# MCU.net
KiCad netlist of a schematic drawn in Altium Designer
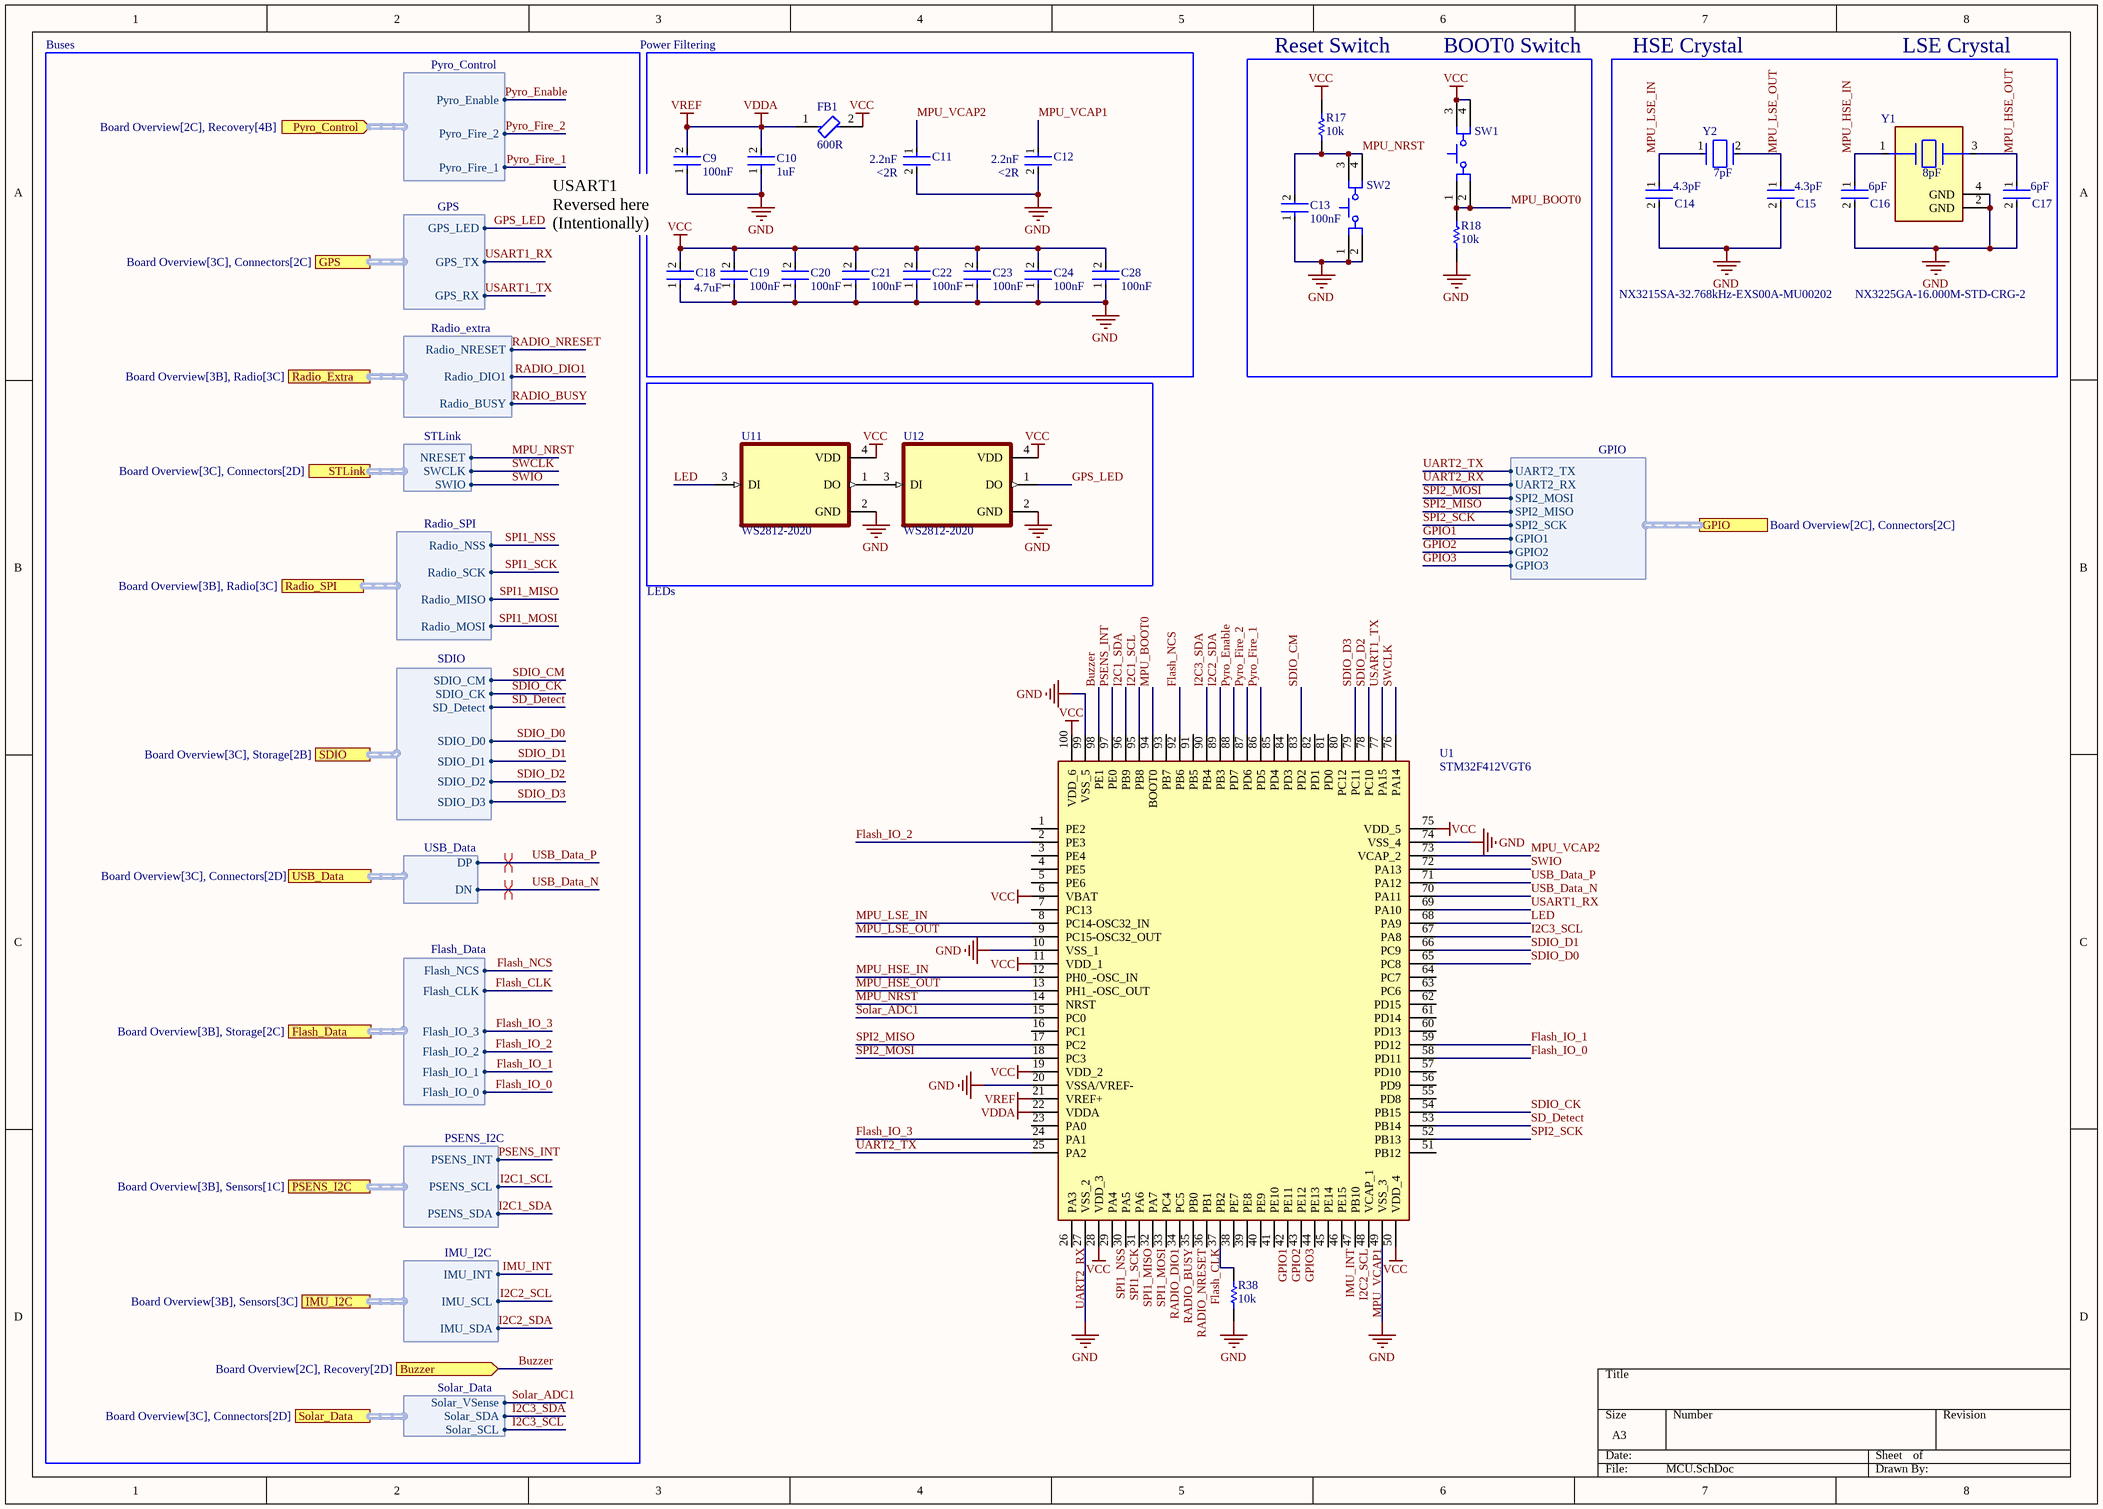
[diagram p0: MCU.SchDoc]

(export (version "E")
  (design (tool "Eeschema 10.0.6"))
  (components
    (comp (ref "C9")
      (value "100nF")
      (footprint "FP-0603-L_1_6_0_15-W_0_81-IPC_C")
      (description "Generic 0603 Capacitor")
      (fields (field (name "LCSC PART #") "C14663") (field (name "TOLERANCE") "10%"))
      (libsource (lib "StrathSEDS") (part "02cd4be3c70576c341d710602a673aa"))
    )
    (comp (ref "C10")
      (value "1uF")
      (footprint "FP-0603-L_1_6_0_15-W_0_81-IPC_C")
      (description "Generic 0603 Capacitor")
      (fields (field (name "LCSC PART #") "C15849") (field (name "TOLERANCE") "10%"))
      (libsource (lib "StrathSEDS") (part "02cd4be3c70576c341d710602a673aa"))
    )
    (comp (ref "C11")
      (value "2.2nF")
      (footprint "FP-0603-L_1_6_0_15-W_0_81-IPC_C")
      (description "Generic 0603 Capacitor")
      (fields
        (field (name "LCSC PART #") "C1604")
        (field (name "TOLERANCE") "10%")
        (field (name "ESR") "<2R")
      )
      (libsource (lib "StrathSEDS") (part "02cd4be3c70576c341d710602a673aa"))
    )
    (comp (ref "C12")
      (value "2.2nF")
      (footprint "FP-0603-L_1_6_0_15-W_0_81-IPC_C")
      (description "Generic 0603 Capacitor")
      (fields
        (field (name "LCSC PART #") "C1604")
        (field (name "TOLERANCE") "10%")
        (field (name "ESR") "<2R")
      )
      (libsource (lib "StrathSEDS") (part "02cd4be3c70576c341d710602a673aa"))
    )
    (comp (ref "C13")
      (value "100nF")
      (footprint "FP-0603-L_1_6_0_15-W_0_81-IPC_C")
      (description "Generic 0603 Capacitor")
      (fields (field (name "LCSC PART #") "C14663") (field (name "TOLERANCE") "10%"))
      (libsource (lib "StrathSEDS") (part "02cd4be3c70576c341d710602a673aa"))
    )
    (comp (ref "C14")
      (value "4.3pF")
      (footprint "FP-CL10-IPC_B")
      (description "50V 4.3pF C0G ±0.25pF 0603 Multilayer Ceramic Capacitors MLCC - SMD/SMT ROHS")
      (fields (field (name "LCSC PART #") "C59526") (field (name "Comment") "0603CG4R3C500NT"))
      (libsource (lib "StrathSEDS Mach 22") (part "b4654b650e69147ec39a6b967a45e02"))
    )
    (comp (ref "C15")
      (value "4.3pF")
      (footprint "FP-CL10-IPC_B")
      (description "50V 4.3pF C0G ±0.25pF 0603 Multilayer Ceramic Capacitors MLCC - SMD/SMT ROHS")
      (fields (field (name "LCSC PART #") "C59526") (field (name "Comment") "0603CG4R3C500NT"))
      (libsource (lib "StrathSEDS Mach 22") (part "b4654b650e69147ec39a6b967a45e02"))
    )
    (comp (ref "C16")
      (value "6pF")
      (footprint "FP-CL10-IPC_B")
      (description "CAP CER 6PF 50V C0G/NP0 0603")
      (fields (field (name "LCSC PART #") "C37474") (field (name "Comment") "CL10C060DB8NNNC"))
      (libsource (lib "StrathSEDS Mach 22") (part "b4654b650e69147ec39a6b967a45e02"))
    )
    (comp (ref "C17")
      (value "6pF")
      (footprint "FP-CL10-IPC_B")
      (description "CAP CER 6PF 50V C0G/NP0 0603")
      (fields (field (name "LCSC PART #") "C37474") (field (name "Comment") "CL10C060DB8NNNC"))
      (libsource (lib "StrathSEDS Mach 22") (part "b4654b650e69147ec39a6b967a45e02"))
    )
    (comp (ref "C18")
      (value "4.7uF")
      (footprint "FP-0603-L_1_6_0_15-W_0_81-IPC_C")
      (description "Generic 0603 Capacitor")
      (fields (field (name "LCSC PART #") "C53987") (field (name "TOLERANCE") "10%"))
      (libsource (lib "StrathSEDS") (part "02cd4be3c70576c341d710602a673aa"))
    )
    (comp (ref "C19")
      (value "100nF")
      (footprint "FP-0603-L_1_6_0_15-W_0_81-IPC_C")
      (description "Generic 0603 Capacitor")
      (fields (field (name "LCSC PART #") "C14663") (field (name "TOLERANCE") "10%"))
      (libsource (lib "StrathSEDS") (part "02cd4be3c70576c341d710602a673aa"))
    )
    (comp (ref "C20")
      (value "100nF")
      (footprint "FP-0603-L_1_6_0_15-W_0_81-IPC_C")
      (description "Generic 0603 Capacitor")
      (fields (field (name "LCSC PART #") "C14663") (field (name "TOLERANCE") "10%"))
      (libsource (lib "StrathSEDS") (part "02cd4be3c70576c341d710602a673aa"))
    )
    (comp (ref "C21")
      (value "100nF")
      (footprint "FP-0603-L_1_6_0_15-W_0_81-IPC_C")
      (description "Generic 0603 Capacitor")
      (fields (field (name "LCSC PART #") "C14663") (field (name "TOLERANCE") "10%"))
      (libsource (lib "StrathSEDS") (part "02cd4be3c70576c341d710602a673aa"))
    )
    (comp (ref "C22")
      (value "100nF")
      (footprint "FP-0603-L_1_6_0_15-W_0_81-IPC_C")
      (description "Generic 0603 Capacitor")
      (fields (field (name "LCSC PART #") "C14663") (field (name "TOLERANCE") "10%"))
      (libsource (lib "StrathSEDS") (part "02cd4be3c70576c341d710602a673aa"))
    )
    (comp (ref "C23")
      (value "100nF")
      (footprint "FP-0603-L_1_6_0_15-W_0_81-IPC_C")
      (description "Generic 0603 Capacitor")
      (fields (field (name "LCSC PART #") "C14663") (field (name "TOLERANCE") "10%"))
      (libsource (lib "StrathSEDS") (part "02cd4be3c70576c341d710602a673aa"))
    )
    (comp (ref "C24")
      (value "100nF")
      (footprint "FP-0603-L_1_6_0_15-W_0_81-IPC_C")
      (description "Generic 0603 Capacitor")
      (fields (field (name "LCSC PART #") "C14663") (field (name "TOLERANCE") "10%"))
      (libsource (lib "StrathSEDS") (part "02cd4be3c70576c341d710602a673aa"))
    )
    (comp (ref "C28")
      (value "100nF")
      (footprint "FP-0603-L_1_6_0_15-W_0_81-IPC_C")
      (description "Generic 0603 Capacitor")
      (fields (field (name "LCSC PART #") "C14663") (field (name "TOLERANCE") "10%"))
      (libsource (lib "StrathSEDS") (part "02cd4be3c70576c341d710602a673aa"))
    )
    (comp (ref "FB1")
      (value "600R")
      (footprint "FP-BLM18-0_15-0_1-t0_6-IPC_B")
      (description "0603 600Ω ±25% DCR=0.45Ω 0.2A")
      (fields (field (name "LCSC PART #") "C1002") (field (name "Comment") "GZ1608D601TF"))
      (libsource (lib "StrathSEDS Mach 22") (part "5f30dd21d616792df468990f7003faa"))
    )
    (comp (ref "R17")
      (value "10k")
      (footprint "RESC1608X55X25ML10T15")
      (fields (field (name "LCSC PART #") "C25804") (field (name "Comment") "0603WAF1002T5E"))
      (libsource (lib "StrathSEDS Mach 22") (part "RES-2"))
    )
    (comp (ref "R18")
      (value "10k")
      (footprint "RESC1608X55X25ML10T15")
      (fields (field (name "LCSC PART #") "C25804") (field (name "Comment") "0603WAF1002T5E"))
      (libsource (lib "StrathSEDS Mach 22") (part "RES-2"))
    )
    (comp (ref "R38")
      (value "10k")
      (footprint "RESC1609X50X30ML8T20")
      (description "Generic 0603 Resistor")
      (fields (field (name "TOLERANCE") "0%") (field (name "LCSC PART #") "C25804"))
      (libsource (lib "StrathSEDS") (part "RES-2"))
    )
    (comp (ref "SW1")
      (value "PTS645SM43SMTR92LFS")
      (footprint "CKCP-PTS645S_V")
      (description "Switch Tactile N.O. SPST Round Button Gull Wing 0.05A 12VDC 100000Cycles 1.57N SMD T/R")
      (fields (field (name "LCSC PART #") "C221880"))
      (libsource (lib "StrathSEDS Mach 22") (part "SW-SPST-NO-4"))
    )
    (comp (ref "SW2")
      (value "PTS645SM43SMTR92LFS")
      (footprint "CKCP-PTS645S_V")
      (description "Switch Tactile N.O. SPST Round Button Gull Wing 0.05A 12VDC 100000Cycles 1.57N SMD T/R")
      (fields (field (name "LCSC PART #") "C221880"))
      (libsource (lib "StrathSEDS Mach 22") (part "SW-SPST-NO-4"))
    )
    (comp (ref "U1")
      (value "STM32F412VGT6")
      (footprint "QFP50P1600X1600X160-100N")
      (fields (field (name "MOUSER PART NUMBER") "511-STM32F412VGT6") (field (name "LCSC PART #") "C727951"))
      (libsource (lib "StrathSEDS") (part "STM32F412VGT6"))
    )
    (comp (ref "U11")
      (value "WS2812-2020")
      (footprint "LED_WS2812-2020")
      (description "Intelligent control LED light source, SMD-4")
      (fields (field (name "MF") "Worldsemi") (field (name "LCSC PART #") "C965555"))
      (libsource (lib "StrathSEDS") (part "WS2812-2020"))
    )
    (comp (ref "U12")
      (value "WS2812-2020")
      (footprint "LED_WS2812-2020")
      (description "Intelligent control LED light source, SMD-4")
      (fields (field (name "MF") "Worldsemi") (field (name "LCSC PART #") "C965555"))
      (libsource (lib "StrathSEDS") (part "WS2812-2020"))
    )
    (comp (ref "Y1")
      (value "NX3225GA-16.000M-STD-CRG-2")
      (footprint "FP-NX3225GA-MFG")
      (description "Crystal 16MHz ±20ppm (Tol) ±30ppm (Stability) 8pF FUND 80Ohm Automotive 4-Pin SMD")
      (fields (field (name "LCSC PART #") "C156247") (field (name "ALTIUM_VALUE") "8pF"))
      (libsource (lib "StrathSEDS Mach 22") (part "6320effb7d3e443b36bf79d8ebe02e5"))
    )
    (comp (ref "Y2")
      (value "NX3215SA-32.768kHz-EXS00A-MU00202")
      (footprint "FP-NX3215SA-MFG")
      (description "Crystal 32.7680KHZ 7PF SMD")
      (fields (field (name "LCSC PART #") "C280830") (field (name "ALTIUM_VALUE") "7pF"))
      (libsource (lib "StrathSEDS Mach 22") (part "c23a69dc6c9e2f18f2079038eb95dd1"))
    )
  )
  (nets
    (net (code "13") (name "/Buzzer") (class "Default")
      (node (ref "U1") (pin "98") (pinfunction "PE1_98") (pintype "passive"))
    )
    (net (code "14") (name "/Flash_CLK") (class "Default")
      (node (ref "U1") (pin "36") (pinfunction "PB1_36") (pintype "passive"))
    )
    (net (code "15") (name "/Flash_IO_0") (class "Default")
      (node (ref "U1") (pin "58") (pinfunction "PD11_58") (pintype "passive"))
    )
    (net (code "16") (name "/Flash_IO_1") (class "Default")
      (node (ref "U1") (pin "59") (pinfunction "PD12_59") (pintype "passive"))
    )
    (net (code "17") (name "/Flash_IO_2") (class "Default")
      (node (ref "U1") (pin "2") (pinfunction "PE3_2") (pintype "passive"))
    )
    (net (code "18") (name "/Flash_IO_3") (class "Default")
      (node (ref "U1") (pin "24") (pinfunction "PA1_24") (pintype "passive"))
    )
    (net (code "19") (name "/Flash_NCS") (class "Default")
      (node (ref "U1") (pin "92") (pinfunction "PB6_92") (pintype "passive"))
    )
    (net (code "20") (name "/GPIO1") (class "Default")
      (node (ref "U1") (pin "41") (pinfunction "PE10_41") (pintype "passive"))
    )
    (net (code "21") (name "/GPIO2") (class "Default")
      (node (ref "U1") (pin "42") (pinfunction "PE11_42") (pintype "passive"))
    )
    (net (code "22") (name "/GPIO3") (class "Default")
      (node (ref "U1") (pin "43") (pinfunction "PE12_43") (pintype "passive"))
    )
    (net (code "23") (name "/GPS_LED") (class "Default")
      (node (ref "U12") (pin "1") (pinfunction "DO_1") (pintype "output"))
    )
    (net (code "24") (name "/I2C1_SCL") (class "Default")
      (node (ref "U1") (pin "95") (pinfunction "PB8_95") (pintype "passive"))
    )
    (net (code "25") (name "/I2C1_SDA") (class "Default")
      (node (ref "U1") (pin "96") (pinfunction "PB9_96") (pintype "passive"))
    )
    (net (code "26") (name "/I2C2_SCL") (class "Default")
      (node (ref "U1") (pin "47") (pinfunction "PB10_47") (pintype "passive"))
    )
    (net (code "27") (name "/I2C2_SDA") (class "Default")
      (node (ref "U1") (pin "89") (pinfunction "PB3_89") (pintype "passive"))
    )
    (net (code "28") (name "/I2C3_SCL") (class "Default")
      (node (ref "U1") (pin "67") (pinfunction "PA8_67") (pintype "passive"))
    )
    (net (code "29") (name "/I2C3_SDA") (class "Default")
      (node (ref "U1") (pin "90") (pinfunction "PB4_90") (pintype "passive"))
    )
    (net (code "30") (name "/IMU_INT") (class "Default")
      (node (ref "U1") (pin "46") (pinfunction "PE15_46") (pintype "passive"))
    )
    (net (code "31") (name "/LED") (class "Default")
      (node (ref "U1") (pin "68") (pinfunction "PA9_68") (pintype "passive"))
      (node (ref "U11") (pin "3") (pinfunction "DI_3") (pintype "input"))
    )
    (net (code "32") (name "/MPU_BOOT0") (class "Default")
      (node (ref "R18") (pin "2") (pinfunction "2_2") (pintype "passive"))
      (node (ref "SW1") (pin "1") (pinfunction "1_1") (pintype "passive"))
      (node (ref "SW1") (pin "2") (pinfunction "2_2") (pintype "passive"))
      (node (ref "U1") (pin "94") (pinfunction "BOOT0_94") (pintype "passive"))
    )
    (net (code "33") (name "/MPU_HSE_IN") (class "Default")
      (node (ref "C16") (pin "1") (pinfunction "1_1") (pintype "passive"))
      (node (ref "U1") (pin "12") (pinfunction "PH0_-OSC_IN_12") (pintype "passive"))
      (node (ref "Y1") (pin "1") (pinfunction "1_1") (pintype "passive"))
    )
    (net (code "34") (name "/MPU_HSE_OUT") (class "Default")
      (node (ref "C17") (pin "1") (pinfunction "1_1") (pintype "passive"))
      (node (ref "U1") (pin "13") (pinfunction "PH1_-OSC_OUT_13") (pintype "passive"))
      (node (ref "Y1") (pin "3") (pinfunction "3_3") (pintype "passive"))
    )
    (net (code "35") (name "/MPU_LSE_IN") (class "Default")
      (node (ref "C14") (pin "1") (pinfunction "1_1") (pintype "passive"))
      (node (ref "U1") (pin "8") (pinfunction "PC14-OSC32_IN_8") (pintype "passive"))
      (node (ref "Y2") (pin "1") (pinfunction "1_1") (pintype "passive"))
    )
    (net (code "36") (name "/MPU_LSE_OUT") (class "Default")
      (node (ref "C15") (pin "1") (pinfunction "1_1") (pintype "passive"))
      (node (ref "U1") (pin "9") (pinfunction "PC15-OSC32_OUT_9") (pintype "passive"))
      (node (ref "Y2") (pin "2") (pinfunction "2_2") (pintype "passive"))
    )
    (net (code "37") (name "/MPU_NRST") (class "Default")
      (node (ref "C13") (pin "2") (pinfunction "2_2") (pintype "passive"))
      (node (ref "R17") (pin "1") (pinfunction "1_1") (pintype "passive"))
      (node (ref "SW2") (pin "3") (pinfunction "3_3") (pintype "passive"))
      (node (ref "SW2") (pin "4") (pinfunction "4_4") (pintype "passive"))
      (node (ref "U1") (pin "14") (pinfunction "NRST_14") (pintype "passive"))
    )
    (net (code "38") (name "/MPU_VCAP1") (class "Default")
      (node (ref "C12") (pin "1") (pinfunction "1_1") (pintype "passive"))
      (node (ref "U1") (pin "48") (pinfunction "VCAP_1_48") (pintype "passive"))
    )
    (net (code "39") (name "/MPU_VCAP2") (class "Default")
      (node (ref "C11") (pin "1") (pinfunction "1_1") (pintype "passive"))
      (node (ref "U1") (pin "73") (pinfunction "VCAP_2_73") (pintype "passive"))
    )
    (net (code "40") (name "/PSENS_INT") (class "Default")
      (node (ref "U1") (pin "97") (pinfunction "PE0_97") (pintype "passive"))
    )
    (net (code "41") (name "/Pyro_Enable") (class "Default")
      (node (ref "U1") (pin "88") (pinfunction "PD7_88") (pintype "passive"))
    )
    (net (code "42") (name "/Pyro_Fire_1") (class "Default")
      (node (ref "U1") (pin "86") (pinfunction "PD5_86") (pintype "passive"))
    )
    (net (code "43") (name "/Pyro_Fire_2") (class "Default")
      (node (ref "U1") (pin "87") (pinfunction "PD6_87") (pintype "passive"))
    )
    (net (code "44") (name "/RADIO_BUSY") (class "Default")
      (node (ref "U1") (pin "34") (pinfunction "PC5_34") (pintype "passive"))
    )
    (net (code "45") (name "/RADIO_DIO1") (class "Default")
      (node (ref "U1") (pin "33") (pinfunction "PC4_33") (pintype "passive"))
    )
    (net (code "46") (name "/RADIO_NRESET") (class "Default")
      (node (ref "U1") (pin "35") (pinfunction "PB0_35") (pintype "passive"))
    )
    (net (code "47") (name "/SDIO_CK") (class "Default")
      (node (ref "U1") (pin "54") (pinfunction "PB15_54") (pintype "passive"))
    )
    (net (code "48") (name "/SDIO_CM") (class "Default")
      (node (ref "U1") (pin "83") (pinfunction "PD2_83") (pintype "passive"))
    )
    (net (code "49") (name "/SDIO_D0") (class "Default")
      (node (ref "U1") (pin "65") (pinfunction "PC8_65") (pintype "passive"))
    )
    (net (code "50") (name "/SDIO_D1") (class "Default")
      (node (ref "U1") (pin "66") (pinfunction "PC9_66") (pintype "passive"))
    )
    (net (code "51") (name "/SDIO_D2") (class "Default")
      (node (ref "U1") (pin "78") (pinfunction "PC10_78") (pintype "passive"))
    )
    (net (code "52") (name "/SDIO_D3") (class "Default")
      (node (ref "U1") (pin "79") (pinfunction "PC11_79") (pintype "passive"))
    )
    (net (code "53") (name "/SD_Detect") (class "Default")
      (node (ref "U1") (pin "53") (pinfunction "PB14_53") (pintype "passive"))
    )
    (net (code "54") (name "/SPI1_MISO") (class "Default")
      (node (ref "U1") (pin "31") (pinfunction "PA6_31") (pintype "passive"))
    )
    (net (code "55") (name "/SPI1_MOSI") (class "Default")
      (node (ref "U1") (pin "32") (pinfunction "PA7_32") (pintype "passive"))
    )
    (net (code "56") (name "/SPI1_NSS") (class "Default")
      (node (ref "U1") (pin "29") (pinfunction "PA4_29") (pintype "passive"))
    )
    (net (code "57") (name "/SPI1_SCK") (class "Default")
      (node (ref "U1") (pin "30") (pinfunction "PA5_30") (pintype "passive"))
    )
    (net (code "58") (name "/SPI2_MISO") (class "Default")
      (node (ref "U1") (pin "17") (pinfunction "PC2_17") (pintype "passive"))
    )
    (net (code "59") (name "/SPI2_MOSI") (class "Default")
      (node (ref "U1") (pin "18") (pinfunction "PC3_18") (pintype "passive"))
    )
    (net (code "60") (name "/SPI2_SCK") (class "Default")
      (node (ref "U1") (pin "52") (pinfunction "PB13_52") (pintype "passive"))
    )
    (net (code "61") (name "/SWCLK") (class "Default")
      (node (ref "U1") (pin "76") (pinfunction "PA14_76") (pintype "passive"))
    )
    (net (code "62") (name "/SWIO") (class "Default")
      (node (ref "U1") (pin "72") (pinfunction "PA13_72") (pintype "passive"))
    )
    (net (code "63") (name "/Solar_ADC1") (class "Default")
      (node (ref "U1") (pin "15") (pinfunction "PC0_15") (pintype "passive"))
    )
    (net (code "64") (name "/UART2_RX") (class "Default")
      (node (ref "U1") (pin "26") (pinfunction "PA3_26") (pintype "passive"))
    )
    (net (code "65") (name "/UART2_TX") (class "Default")
      (node (ref "U1") (pin "25") (pinfunction "PA2_25") (pintype "passive"))
    )
    (net (code "66") (name "/USART1_RX") (class "Default")
      (node (ref "U1") (pin "69") (pinfunction "PA10_69") (pintype "passive"))
    )
    (net (code "67") (name "/USART1_TX") (class "Default")
      (node (ref "U1") (pin "77") (pinfunction "PA15_77") (pintype "passive"))
    )
    (net (code "68") (name "/USB_Data_N") (class "Default")
      (node (ref "U1") (pin "70") (pinfunction "PA11_70") (pintype "passive"))
    )
    (net (code "69") (name "/USB_Data_P") (class "Default")
      (node (ref "U1") (pin "71") (pinfunction "PA12_71") (pintype "passive"))
    )
    (net (code "82") (name "GND") (class "Default")
      (node (ref "C10") (pin "1") (pinfunction "1_1") (pintype "passive"))
      (node (ref "C11") (pin "2") (pinfunction "2_2") (pintype "passive"))
      (node (ref "C12") (pin "2") (pinfunction "2_2") (pintype "passive"))
      (node (ref "C13") (pin "1") (pinfunction "1_1") (pintype "passive"))
      (node (ref "C14") (pin "2") (pinfunction "2_2") (pintype "passive"))
      (node (ref "C15") (pin "2") (pinfunction "2_2") (pintype "passive"))
      (node (ref "C16") (pin "2") (pinfunction "2_2") (pintype "passive"))
      (node (ref "C17") (pin "2") (pinfunction "2_2") (pintype "passive"))
      (node (ref "C18") (pin "1") (pinfunction "1_1") (pintype "passive"))
      (node (ref "C19") (pin "1") (pinfunction "1_1") (pintype "passive"))
      (node (ref "C20") (pin "1") (pinfunction "1_1") (pintype "passive"))
      (node (ref "C21") (pin "1") (pinfunction "1_1") (pintype "passive"))
      (node (ref "C22") (pin "1") (pinfunction "1_1") (pintype "passive"))
      (node (ref "C23") (pin "1") (pinfunction "1_1") (pintype "passive"))
      (node (ref "C24") (pin "1") (pinfunction "1_1") (pintype "passive"))
      (node (ref "C28") (pin "1") (pinfunction "1_1") (pintype "passive"))
      (node (ref "C9") (pin "1") (pinfunction "1_1") (pintype "passive"))
      (node (ref "R18") (pin "1") (pinfunction "1_1") (pintype "passive"))
      (node (ref "R38") (pin "1") (pinfunction "1_1") (pintype "passive"))
      (node (ref "SW2") (pin "1") (pinfunction "1_1") (pintype "passive"))
      (node (ref "SW2") (pin "2") (pinfunction "2_2") (pintype "passive"))
      (node (ref "U1") (pin "10") (pinfunction "VSS_1_10") (pintype "passive"))
      (node (ref "U1") (pin "20") (pinfunction "VSSA/VREF-_20") (pintype "passive"))
      (node (ref "U1") (pin "27") (pinfunction "VSS_2_27") (pintype "passive"))
      (node (ref "U1") (pin "49") (pinfunction "VSS_3_49") (pintype "passive"))
      (node (ref "U1") (pin "74") (pinfunction "VSS_4_74") (pintype "passive"))
      (node (ref "U1") (pin "99") (pinfunction "VSS_5_99") (pintype "passive"))
      (node (ref "U11") (pin "2") (pinfunction "GND_2") (pintype "power_in"))
      (node (ref "U12") (pin "2") (pinfunction "GND_2") (pintype "power_in"))
      (node (ref "Y1") (pin "2") (pinfunction "GND_2") (pintype "power_in"))
      (node (ref "Y1") (pin "4") (pinfunction "GND_4") (pintype "power_in"))
    )
    (net (code "83") (name "Net-(U1-PB2)") (class "Default")
      (node (ref "R38") (pin "2") (pinfunction "2_2") (pintype "passive"))
      (node (ref "U1") (pin "37") (pinfunction "PB2_37") (pintype "passive"))
    )
    (net (code "84") (name "Net-(U11-DO)") (class "Default")
      (node (ref "U11") (pin "1") (pinfunction "DO_1") (pintype "output"))
      (node (ref "U12") (pin "3") (pinfunction "DI_3") (pintype "input"))
    )
    (net (code "85") (name "VCC") (class "Default")
      (node (ref "C18") (pin "2") (pinfunction "2_2") (pintype "passive"))
      (node (ref "C19") (pin "2") (pinfunction "2_2") (pintype "passive"))
      (node (ref "C20") (pin "2") (pinfunction "2_2") (pintype "passive"))
      (node (ref "C21") (pin "2") (pinfunction "2_2") (pintype "passive"))
      (node (ref "C22") (pin "2") (pinfunction "2_2") (pintype "passive"))
      (node (ref "C23") (pin "2") (pinfunction "2_2") (pintype "passive"))
      (node (ref "C24") (pin "2") (pinfunction "2_2") (pintype "passive"))
      (node (ref "C28") (pin "2") (pinfunction "2_2") (pintype "passive"))
      (node (ref "FB1") (pin "2") (pinfunction "2_2") (pintype "passive"))
      (node (ref "R17") (pin "2") (pinfunction "2_2") (pintype "passive"))
      (node (ref "SW1") (pin "3") (pinfunction "3_3") (pintype "passive"))
      (node (ref "SW1") (pin "4") (pinfunction "4_4") (pintype "passive"))
      (node (ref "U1") (pin "100") (pinfunction "VDD_6_100") (pintype "passive"))
      (node (ref "U1") (pin "11") (pinfunction "VDD_1_11") (pintype "passive"))
      (node (ref "U1") (pin "19") (pinfunction "VDD_2_19") (pintype "passive"))
      (node (ref "U1") (pin "28") (pinfunction "VDD_3_28") (pintype "passive"))
      (node (ref "U1") (pin "50") (pinfunction "VDD_4_50") (pintype "passive"))
      (node (ref "U1") (pin "6") (pinfunction "VBAT_6") (pintype "passive"))
      (node (ref "U1") (pin "75") (pinfunction "VDD_5_75") (pintype "passive"))
      (node (ref "U11") (pin "4") (pinfunction "VDD_4") (pintype "power_in"))
      (node (ref "U12") (pin "4") (pinfunction "VDD_4") (pintype "power_in"))
    )
    (net (code "86") (name "VDDA") (class "Default")
      (node (ref "C10") (pin "2") (pinfunction "2_2") (pintype "passive"))
      (node (ref "C9") (pin "2") (pinfunction "2_2") (pintype "passive"))
      (node (ref "FB1") (pin "1") (pinfunction "1_1") (pintype "passive"))
      (node (ref "U1") (pin "21") (pinfunction "VREF+_21") (pintype "passive"))
      (node (ref "U1") (pin "22") (pinfunction "VDDA_22") (pintype "passive"))
    )
    (net (code "87") (name "unconnected-(U1-PA0-Pad23)") (class "Default")
      (node (ref "U1") (pin "23") (pinfunction "PA0_23") (pintype "passive"))
    )
    (net (code "88") (name "unconnected-(U1-PB5-Pad91)") (class "Default")
      (node (ref "U1") (pin "91") (pinfunction "PB5_91") (pintype "passive"))
    )
    (net (code "89") (name "unconnected-(U1-PB7-Pad93)") (class "Default")
      (node (ref "U1") (pin "93") (pinfunction "PB7_93") (pintype "passive"))
    )
    (net (code "90") (name "unconnected-(U1-PB12-Pad51)") (class "Default")
      (node (ref "U1") (pin "51") (pinfunction "PB12_51") (pintype "passive"))
    )
    (net (code "91") (name "unconnected-(U1-PC1-Pad16)") (class "Default")
      (node (ref "U1") (pin "16") (pinfunction "PC1_16") (pintype "passive"))
    )
    (net (code "92") (name "unconnected-(U1-PC6-Pad63)") (class "Default")
      (node (ref "U1") (pin "63") (pinfunction "PC6_63") (pintype "passive"))
    )
    (net (code "93") (name "unconnected-(U1-PC7-Pad64)") (class "Default")
      (node (ref "U1") (pin "64") (pinfunction "PC7_64") (pintype "passive"))
    )
    (net (code "94") (name "unconnected-(U1-PC12-Pad80)") (class "Default")
      (node (ref "U1") (pin "80") (pinfunction "PC12_80") (pintype "passive"))
    )
    (net (code "95") (name "unconnected-(U1-PC13-Pad7)") (class "Default")
      (node (ref "U1") (pin "7") (pinfunction "PC13_7") (pintype "passive"))
    )
    (net (code "96") (name "unconnected-(U1-PD0-Pad81)") (class "Default")
      (node (ref "U1") (pin "81") (pinfunction "PD0_81") (pintype "passive"))
    )
    (net (code "97") (name "unconnected-(U1-PD1-Pad82)") (class "Default")
      (node (ref "U1") (pin "82") (pinfunction "PD1_82") (pintype "passive"))
    )
    (net (code "98") (name "unconnected-(U1-PD3-Pad84)") (class "Default")
      (node (ref "U1") (pin "84") (pinfunction "PD3_84") (pintype "passive"))
    )
    (net (code "99") (name "unconnected-(U1-PD4-Pad85)") (class "Default")
      (node (ref "U1") (pin "85") (pinfunction "PD4_85") (pintype "passive"))
    )
    (net (code "100") (name "unconnected-(U1-PD8-Pad55)") (class "Default")
      (node (ref "U1") (pin "55") (pinfunction "PD8_55") (pintype "passive"))
    )
    (net (code "101") (name "unconnected-(U1-PD9-Pad56)") (class "Default")
      (node (ref "U1") (pin "56") (pinfunction "PD9_56") (pintype "passive"))
    )
    (net (code "102") (name "unconnected-(U1-PD10-Pad57)") (class "Default")
      (node (ref "U1") (pin "57") (pinfunction "PD10_57") (pintype "passive"))
    )
    (net (code "103") (name "unconnected-(U1-PD13-Pad60)") (class "Default")
      (node (ref "U1") (pin "60") (pinfunction "PD13_60") (pintype "passive"))
    )
    (net (code "104") (name "unconnected-(U1-PD14-Pad61)") (class "Default")
      (node (ref "U1") (pin "61") (pinfunction "PD14_61") (pintype "passive"))
    )
    (net (code "105") (name "unconnected-(U1-PD15-Pad62)") (class "Default")
      (node (ref "U1") (pin "62") (pinfunction "PD15_62") (pintype "passive"))
    )
    (net (code "106") (name "unconnected-(U1-PE2-Pad1)") (class "Default")
      (node (ref "U1") (pin "1") (pinfunction "PE2_1") (pintype "passive"))
    )
    (net (code "107") (name "unconnected-(U1-PE4-Pad3)") (class "Default")
      (node (ref "U1") (pin "3") (pinfunction "PE4_3") (pintype "passive"))
    )
    (net (code "108") (name "unconnected-(U1-PE5-Pad4)") (class "Default")
      (node (ref "U1") (pin "4") (pinfunction "PE5_4") (pintype "passive"))
    )
    (net (code "109") (name "unconnected-(U1-PE6-Pad5)") (class "Default")
      (node (ref "U1") (pin "5") (pinfunction "PE6_5") (pintype "passive"))
    )
    (net (code "110") (name "unconnected-(U1-PE7-Pad38)") (class "Default")
      (node (ref "U1") (pin "38") (pinfunction "PE7_38") (pintype "passive"))
    )
    (net (code "111") (name "unconnected-(U1-PE8-Pad39)") (class "Default")
      (node (ref "U1") (pin "39") (pinfunction "PE8_39") (pintype "passive"))
    )
    (net (code "112") (name "unconnected-(U1-PE9-Pad40)") (class "Default")
      (node (ref "U1") (pin "40") (pinfunction "PE9_40") (pintype "passive"))
    )
    (net (code "113") (name "unconnected-(U1-PE13-Pad44)") (class "Default")
      (node (ref "U1") (pin "44") (pinfunction "PE13_44") (pintype "passive"))
    )
    (net (code "114") (name "unconnected-(U1-PE14-Pad45)") (class "Default")
      (node (ref "U1") (pin "45") (pinfunction "PE14_45") (pintype "passive"))
    )
  )
)
